# WaterLevelMonitor_v1.net
KiCad netlist of a schematic drawn in EAGLE
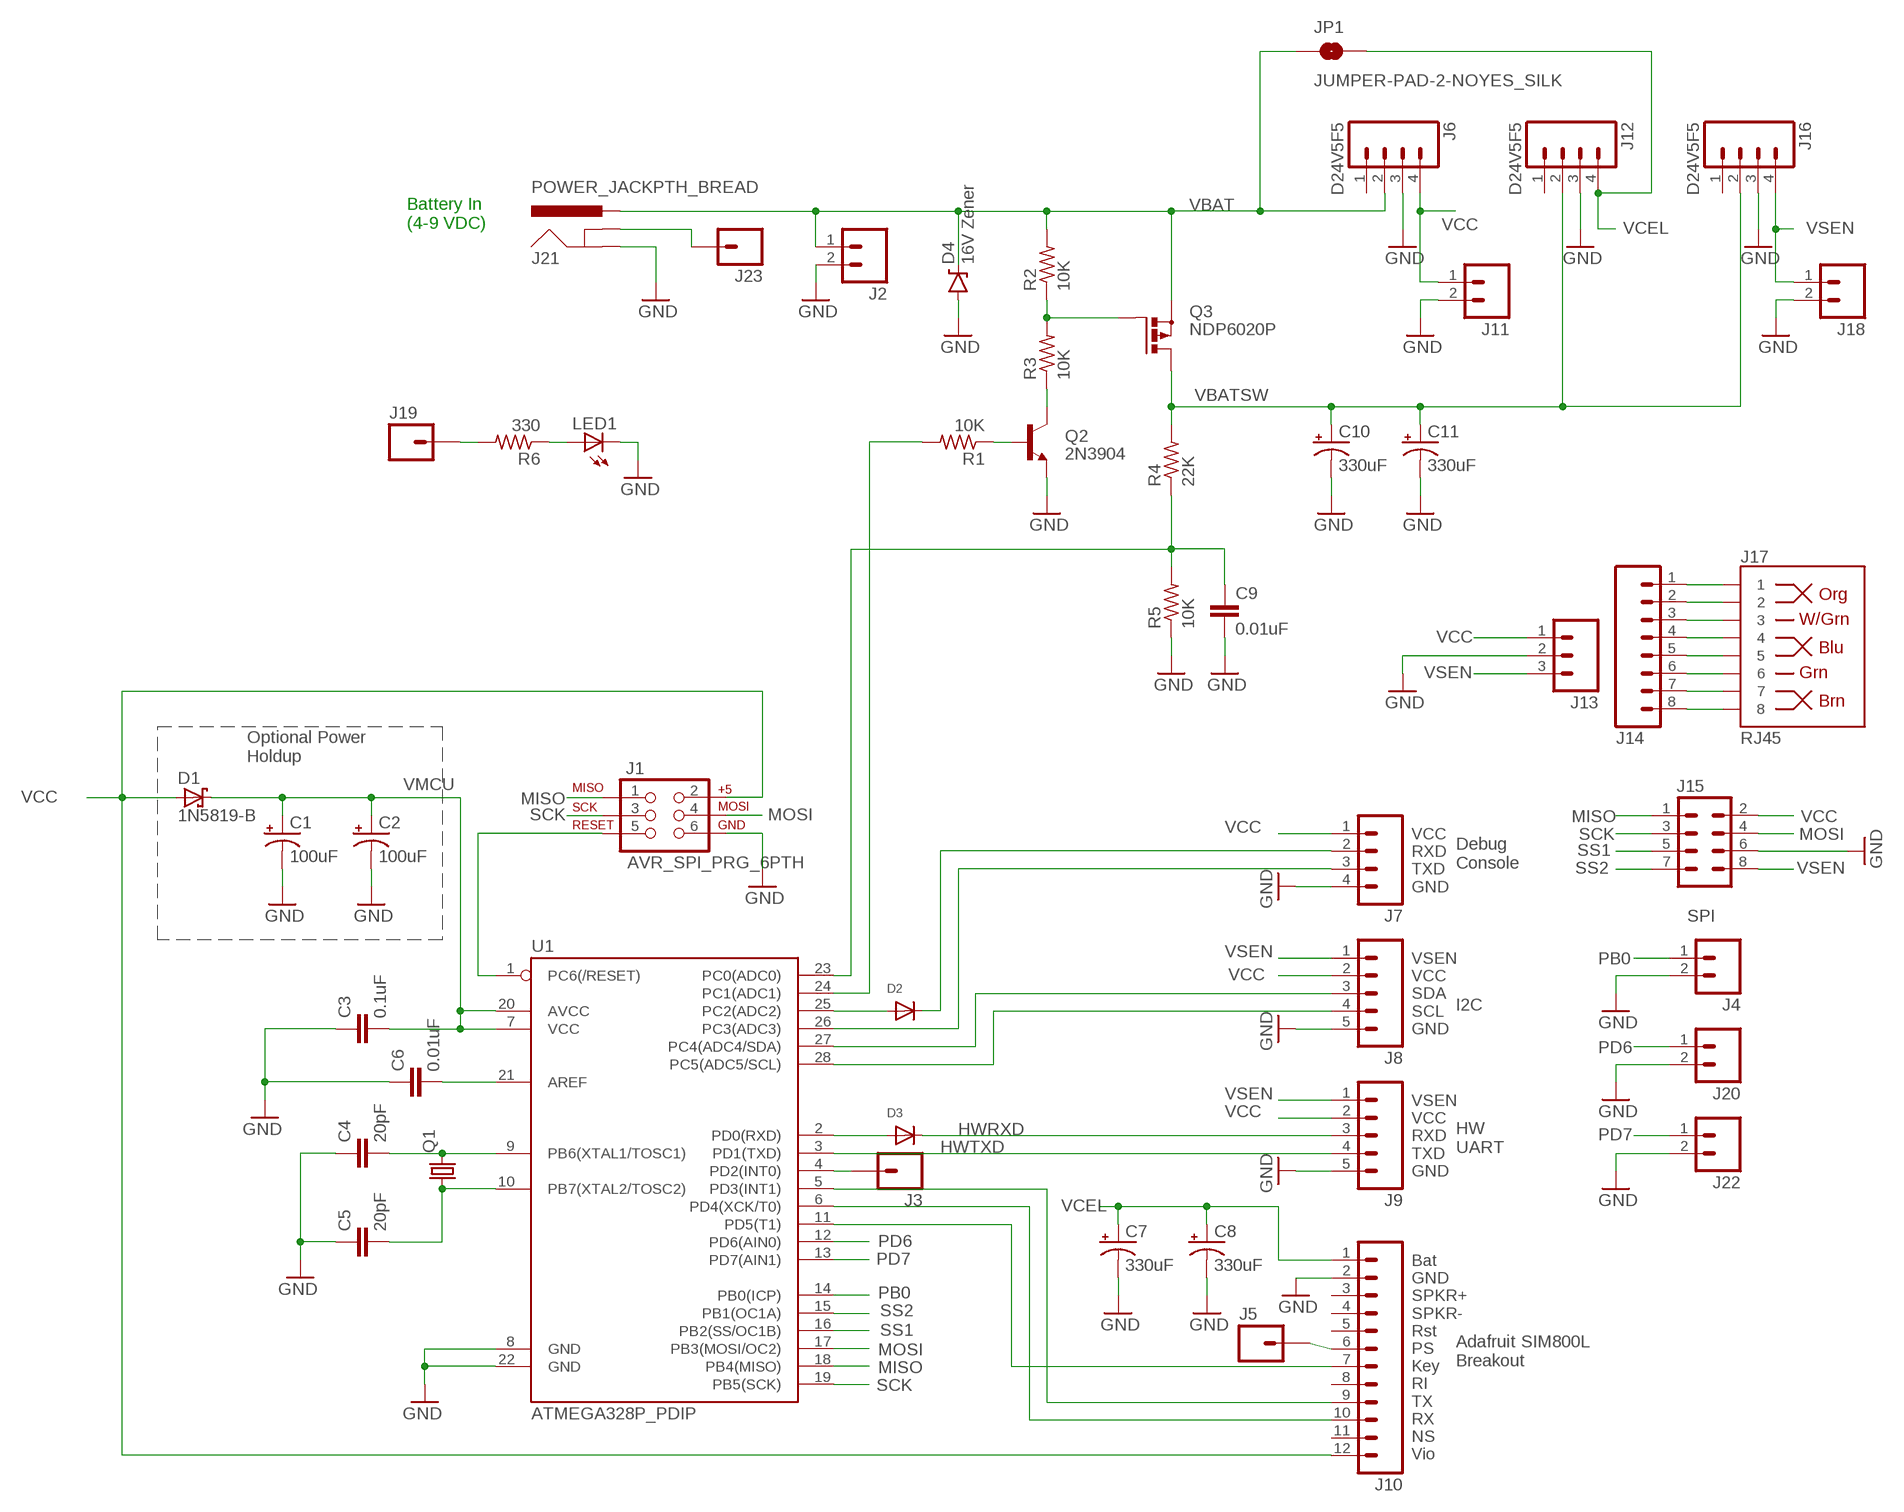
[diagram p0: schematic, sheet 1]

(export (version "E")
  (design (tool "Eeschema 10.0.6"))
  (components
    (comp (ref "C1")
      (value "100uF")
      (footprint "eagle-import:CPOL-RADIAL-100UF-25V")
      (libsource (lib "eagle-import") (part "CAP_POLPTH1"))
    )
    (comp (ref "C2")
      (value "100uF")
      (footprint "eagle-import:CPOL-RADIAL-100UF-25V")
      (libsource (lib "eagle-import") (part "CAP_POLPTH1"))
    )
    (comp (ref "C3")
      (value "0.1uF")
      (footprint "eagle-import:CAP-PTH-SMALL")
      (libsource (lib "eagle-import") (part "CAPPTH"))
    )
    (comp (ref "C4")
      (value "20pF")
      (footprint "eagle-import:CAP-PTH-SMALL")
      (libsource (lib "eagle-import") (part "CAPPTH"))
    )
    (comp (ref "C5")
      (value "20pF")
      (footprint "eagle-import:CAP-PTH-SMALL")
      (libsource (lib "eagle-import") (part "CAPPTH"))
    )
    (comp (ref "C6")
      (value "0.01uF")
      (footprint "eagle-import:CAP-PTH-5MM")
      (libsource (lib "eagle-import") (part "SparkFun-Passives_CAPPTH1"))
    )
    (comp (ref "C7")
      (value "330uF")
      (footprint "eagle-import:CPOL-RADIAL-100UF-25V")
      (libsource (lib "eagle-import") (part "CAP_POLPTH1"))
    )
    (comp (ref "C8")
      (value "330uF")
      (footprint "eagle-import:CPOL-RADIAL-100UF-25V")
      (libsource (lib "eagle-import") (part "CAP_POLPTH1"))
    )
    (comp (ref "C9")
      (value "0.01uF")
      (footprint "eagle-import:CAP-PTH-5MM")
      (libsource (lib "eagle-import") (part "SparkFun-Passives_CAPPTH1"))
    )
    (comp (ref "C10")
      (value "330uF")
      (footprint "eagle-import:CPOL-RADIAL-100UF-25V")
      (libsource (lib "eagle-import") (part "CAP_POLPTH1"))
    )
    (comp (ref "C11")
      (value "330uF")
      (footprint "eagle-import:CPOL-RADIAL-100UF-25V")
      (libsource (lib "eagle-import") (part "CAP_POLPTH1"))
    )
    (comp (ref "D1")
      (value "1N5819-B")
      (footprint "eagle-import:DO41-7.6")
      (libsource (lib "eagle-import") (part "1N5819-B"))
    )
    (comp (ref "D2")
      (value "DIODEDO-1N4148")
      (footprint "eagle-import:DO-1N4148")
      (libsource (lib "eagle-import") (part "DIODEDO-1N4148"))
    )
    (comp (ref "D3")
      (value "DIODEDO-1N4148")
      (footprint "eagle-import:DO-1N4148")
      (libsource (lib "eagle-import") (part "DIODEDO-1N4148"))
    )
    (comp (ref "D4")
      (value "16V Zener")
      (footprint "eagle-import:DIODE-ZENER")
      (libsource (lib "eagle-import") (part "DIODE-ZENERPTH"))
    )
    (comp (ref "J1")
      (value "AVR_SPI_PRG_6PTH")
      (footprint "eagle-import:2X3")
      (libsource (lib "eagle-import") (part "AVR_SPI_PRG_6PTH"))
    )
    (comp (ref "J2")
      (value "M02PTH")
      (footprint "eagle-import:1X02")
      (libsource (lib "eagle-import") (part "M02PTH"))
    )
    (comp (ref "J3")
      (value "M01PTH_NO_SILK_YES_STOP")
      (footprint "eagle-import:1X01_NO_SILK")
      (libsource (lib "eagle-import") (part "M01PTH_NO_SILK_YES_STOP"))
    )
    (comp (ref "J4")
      (value "M021X02_NO_SILK")
      (footprint "eagle-import:1X02_NO_SILK")
      (libsource (lib "eagle-import") (part "M021X02_NO_SILK"))
    )
    (comp (ref "J5")
      (value "M01PTH_NO_SILK_YES_STOP")
      (footprint "eagle-import:1X01_NO_SILK")
      (libsource (lib "eagle-import") (part "M01PTH_NO_SILK_YES_STOP"))
    )
    (comp (ref "J6")
      (value "D24V5F5")
      (footprint "eagle-import:1X04")
      (libsource (lib "eagle-import") (part "M04PTH"))
    )
    (comp (ref "J7")
      (value "M04PTH")
      (footprint "eagle-import:1X04")
      (libsource (lib "eagle-import") (part "M04PTH"))
    )
    (comp (ref "J8")
      (value "M05PTH")
      (footprint "eagle-import:1X05")
      (libsource (lib "eagle-import") (part "M05PTH"))
    )
    (comp (ref "J9")
      (value "M05PTH")
      (footprint "eagle-import:1X05")
      (libsource (lib "eagle-import") (part "M05PTH"))
    )
    (comp (ref "J10")
      (value "M12PTH")
      (footprint "eagle-import:1X12")
      (libsource (lib "eagle-import") (part "M12PTH"))
    )
    (comp (ref "J11")
      (value "M02PTH")
      (footprint "eagle-import:1X02")
      (libsource (lib "eagle-import") (part "M02PTH"))
    )
    (comp (ref "J12")
      (value "D24V5F5")
      (footprint "eagle-import:1X04")
      (libsource (lib "eagle-import") (part "M04PTH"))
    )
    (comp (ref "J13")
      (value "M03PTH")
      (footprint "eagle-import:1X03")
      (libsource (lib "eagle-import") (part "M03PTH"))
    )
    (comp (ref "J14")
      (value "M08SILK_FEMALE_PTH")
      (footprint "eagle-import:1X08")
      (libsource (lib "eagle-import") (part "M08SILK_FEMALE_PTH"))
    )
    (comp (ref "J15")
      (value "M04X2")
      (footprint "eagle-import:2X4")
      (libsource (lib "eagle-import") (part "M04X2"))
    )
    (comp (ref "J16")
      (value "D24V5F5")
      (footprint "eagle-import:1X04")
      (libsource (lib "eagle-import") (part "M04PTH"))
    )
    (comp (ref "J17")
      (value "RJ45")
      (footprint "eagle-import:RJ45-8")
      (libsource (lib "eagle-import") (part "RJ45-8PTH"))
    )
    (comp (ref "J18")
      (value "M02PTH")
      (footprint "eagle-import:1X02")
      (libsource (lib "eagle-import") (part "M02PTH"))
    )
    (comp (ref "J19")
      (value "M01PTH_NO_SILK_YES_STOP")
      (footprint "eagle-import:1X01_NO_SILK")
      (libsource (lib "eagle-import") (part "M01PTH_NO_SILK_YES_STOP"))
    )
    (comp (ref "J20")
      (value "M021X02_NO_SILK")
      (footprint "eagle-import:1X02_NO_SILK")
      (libsource (lib "eagle-import") (part "M021X02_NO_SILK"))
    )
    (comp (ref "J21")
      (value "POWER_JACKPTH_BREAD")
      (footprint "eagle-import:POWER_JACK_PTH_BREAD")
      (libsource (lib "eagle-import") (part "POWER_JACKPTH_BREAD"))
    )
    (comp (ref "J22")
      (value "M021X02_NO_SILK")
      (footprint "eagle-import:1X02_NO_SILK")
      (libsource (lib "eagle-import") (part "M021X02_NO_SILK"))
    )
    (comp (ref "J23")
      (value "M01PTH_NO_SILK_YES_STOP")
      (footprint "eagle-import:1X01_NO_SILK")
      (libsource (lib "eagle-import") (part "M01PTH_NO_SILK_YES_STOP"))
    )
    (comp (ref "JP1")
      (value "JUMPER-PAD-2-NOYES_SILK")
      (footprint "eagle-import:PAD-JUMPER-2-NO_YES_SILK")
      (libsource (lib "eagle-import") (part "JUMPER-PAD-2-NOYES_SILK"))
    )
    (comp (ref "LED1")
      (value "LED5MM")
      (footprint "eagle-import:LED5MM")
      (libsource (lib "eagle-import") (part "LED5MM"))
    )
    (comp (ref "Q1")
      (value "CRYSTALHC49U-V")
      (footprint "eagle-import:HC49U-V")
      (libsource (lib "eagle-import") (part "CRYSTALHC49U-V"))
    )
    (comp (ref "Q2")
      (value "2N3904")
      (footprint "eagle-import:TO-92-AMMO")
      (libsource (lib "eagle-import") (part "TRANSISTOR_NPNTO-92-AMMO"))
    )
    (comp (ref "Q3")
      (value "NDP6020P")
      (footprint "eagle-import:TO220BV")
      (libsource (lib "eagle-import") (part "PMOSFET_PTO220BV"))
    )
    (comp (ref "R1")
      (value "10K")
      (footprint "eagle-import:0204_5")
      (libsource (lib "eagle-import") (part "R-US_0204/5"))
    )
    (comp (ref "R2")
      (value "10K")
      (footprint "eagle-import:0204_5")
      (libsource (lib "eagle-import") (part "R-US_0204/5"))
    )
    (comp (ref "R3")
      (value "10K")
      (footprint "eagle-import:0204_5")
      (libsource (lib "eagle-import") (part "R-US_0204/5"))
    )
    (comp (ref "R4")
      (value "22K")
      (footprint "eagle-import:0204_5")
      (libsource (lib "eagle-import") (part "R-US_0204/5"))
    )
    (comp (ref "R5")
      (value "10K")
      (footprint "eagle-import:0204_5")
      (libsource (lib "eagle-import") (part "R-US_0204/5"))
    )
    (comp (ref "R6")
      (value "330")
      (footprint "eagle-import:0204_5")
      (libsource (lib "eagle-import") (part "R-US_0204/5"))
    )
    (comp (ref "U1")
      (value "ATMEGA328P_PDIP")
      (footprint "eagle-import:DIL28-3")
      (libsource (lib "eagle-import") (part "ATMEGA328P_PDIP"))
    )
  )
  (nets
    (net (code "1") (name "/HWRXD") (class "Default")
      (node (ref "D3") (pin "C") (pinfunction "C_C") (pintype "passive"))
      (node (ref "J9") (pin "3") (pinfunction "3_3") (pintype "passive"))
    )
    (net (code "2") (name "/HWTXD") (class "Default")
      (node (ref "J9") (pin "4") (pinfunction "4_4") (pintype "passive"))
      (node (ref "U1") (pin "3") (pinfunction "PD1(TXD)_3") (pintype "bidirectional"))
    )
    (net (code "3") (name "/MISO") (class "Default")
      (node (ref "J1") (pin "1") (pinfunction "1_1") (pintype "passive"))
      (node (ref "J15") (pin "1") (pinfunction "1_1") (pintype "passive"))
      (node (ref "U1") (pin "18") (pinfunction "PB4(MISO)_18") (pintype "bidirectional"))
    )
    (net (code "4") (name "/MOSI") (class "Default")
      (node (ref "J1") (pin "4") (pinfunction "4_4") (pintype "passive"))
      (node (ref "J15") (pin "4") (pinfunction "4_4") (pintype "passive"))
      (node (ref "U1") (pin "17") (pinfunction "PB3(MOSI/OC2)_17") (pintype "bidirectional"))
    )
    (net (code "5") (name "/PB0") (class "Default")
      (node (ref "J4") (pin "1") (pinfunction "1_1") (pintype "passive"))
      (node (ref "U1") (pin "14") (pinfunction "PB0(ICP)_14") (pintype "bidirectional"))
    )
    (net (code "6") (name "/PD6") (class "Default")
      (node (ref "J20") (pin "1") (pinfunction "1_1") (pintype "passive"))
      (node (ref "U1") (pin "12") (pinfunction "PD6(AIN0)_12") (pintype "bidirectional"))
    )
    (net (code "7") (name "/PD7") (class "Default")
      (node (ref "J22") (pin "1") (pinfunction "1_1") (pintype "passive"))
      (node (ref "U1") (pin "13") (pinfunction "PD7(AIN1)_13") (pintype "bidirectional"))
    )
    (net (code "8") (name "/SCK") (class "Default")
      (node (ref "J1") (pin "3") (pinfunction "3_3") (pintype "passive"))
      (node (ref "J15") (pin "3") (pinfunction "3_3") (pintype "passive"))
      (node (ref "U1") (pin "19") (pinfunction "PB5(SCK)_19") (pintype "bidirectional"))
    )
    (net (code "9") (name "/SS1") (class "Default")
      (node (ref "J15") (pin "5") (pinfunction "5_5") (pintype "passive"))
      (node (ref "U1") (pin "16") (pinfunction "PB2(SS/OC1B)_16") (pintype "bidirectional"))
    )
    (net (code "10") (name "/SS2") (class "Default")
      (node (ref "J15") (pin "7") (pinfunction "7_7") (pintype "passive"))
      (node (ref "U1") (pin "15") (pinfunction "PB1(OC1A)_15") (pintype "bidirectional"))
    )
    (net (code "11") (name "/VBAT") (class "Default")
      (node (ref "D4") (pin "P$1") (pinfunction "C_P$1") (pintype "passive"))
      (node (ref "J2") (pin "1") (pinfunction "1_1") (pintype "passive"))
      (node (ref "J21") (pin "PWR") (pinfunction "PWR_PWR") (pintype "bidirectional"))
      (node (ref "J6") (pin "2") (pinfunction "2_2") (pintype "passive"))
      (node (ref "JP1") (pin "1") (pinfunction "1_1") (pintype "passive"))
      (node (ref "Q3") (pin "S") (pinfunction "S_S") (pintype "passive"))
      (node (ref "R2") (pin "2") (pinfunction "2_2") (pintype "passive"))
    )
    (net (code "12") (name "/VBATSW") (class "Default")
      (node (ref "C10") (pin "1") (pinfunction "+_1") (pintype "passive"))
      (node (ref "C11") (pin "1") (pinfunction "+_1") (pintype "passive"))
      (node (ref "J12") (pin "2") (pinfunction "2_2") (pintype "passive"))
      (node (ref "J16") (pin "2") (pinfunction "2_2") (pintype "passive"))
      (node (ref "Q3") (pin "D") (pinfunction "D_D") (pintype "passive"))
      (node (ref "R4") (pin "2") (pinfunction "2_2") (pintype "passive"))
    )
    (net (code "13") (name "/VCC") (class "Default")
      (node (ref "D1") (pin "A") (pinfunction "A_A") (pintype "passive"))
      (node (ref "J1") (pin "2") (pinfunction "2_2") (pintype "passive"))
      (node (ref "J10") (pin "12") (pinfunction "12_12") (pintype "passive"))
      (node (ref "J11") (pin "1") (pinfunction "1_1") (pintype "passive"))
      (node (ref "J13") (pin "1") (pinfunction "1_1") (pintype "passive"))
      (node (ref "J15") (pin "2") (pinfunction "2_2") (pintype "passive"))
      (node (ref "J6") (pin "4") (pinfunction "4_4") (pintype "passive"))
      (node (ref "J7") (pin "1") (pinfunction "1_1") (pintype "passive"))
      (node (ref "J8") (pin "2") (pinfunction "2_2") (pintype "passive"))
      (node (ref "J9") (pin "2") (pinfunction "2_2") (pintype "passive"))
    )
    (net (code "14") (name "/VCEL") (class "Default")
      (node (ref "C7") (pin "1") (pinfunction "+_1") (pintype "passive"))
      (node (ref "C8") (pin "1") (pinfunction "+_1") (pintype "passive"))
      (node (ref "J10") (pin "1") (pinfunction "1_1") (pintype "passive"))
      (node (ref "J12") (pin "4") (pinfunction "4_4") (pintype "passive"))
      (node (ref "JP1") (pin "2") (pinfunction "2_2") (pintype "passive"))
    )
    (net (code "15") (name "/VMCU") (class "Default")
      (node (ref "C1") (pin "1") (pinfunction "+_1") (pintype "passive"))
      (node (ref "C2") (pin "1") (pinfunction "+_1") (pintype "passive"))
      (node (ref "C3") (pin "2") (pinfunction "2_2") (pintype "passive"))
      (node (ref "D1") (pin "C") (pinfunction "C_C") (pintype "passive"))
      (node (ref "U1") (pin "20") (pinfunction "AVCC_20") (pintype "bidirectional"))
      (node (ref "U1") (pin "7") (pinfunction "VCC_7") (pintype "bidirectional"))
    )
    (net (code "16") (name "/VSEN") (class "Default")
      (node (ref "J13") (pin "3") (pinfunction "3_3") (pintype "passive"))
      (node (ref "J15") (pin "8") (pinfunction "8_8") (pintype "passive"))
      (node (ref "J16") (pin "4") (pinfunction "4_4") (pintype "passive"))
      (node (ref "J18") (pin "1") (pinfunction "1_1") (pintype "passive"))
      (node (ref "J8") (pin "1") (pinfunction "1_1") (pintype "passive"))
      (node (ref "J9") (pin "1") (pinfunction "1_1") (pintype "passive"))
    )
    (net (code "17") (name "GND") (class "Default")
      (node (ref "C1") (pin "2") (pinfunction "-_2") (pintype "passive"))
      (node (ref "C10") (pin "2") (pinfunction "-_2") (pintype "passive"))
      (node (ref "C11") (pin "2") (pinfunction "-_2") (pintype "passive"))
      (node (ref "C2") (pin "2") (pinfunction "-_2") (pintype "passive"))
      (node (ref "C3") (pin "1") (pinfunction "1_1") (pintype "passive"))
      (node (ref "C4") (pin "1") (pinfunction "1_1") (pintype "passive"))
      (node (ref "C5") (pin "1") (pinfunction "1_1") (pintype "passive"))
      (node (ref "C6") (pin "1") (pinfunction "1_1") (pintype "passive"))
      (node (ref "C7") (pin "2") (pinfunction "-_2") (pintype "passive"))
      (node (ref "C8") (pin "2") (pinfunction "-_2") (pintype "passive"))
      (node (ref "C9") (pin "2") (pinfunction "2_2") (pintype "passive"))
      (node (ref "D4") (pin "P$2") (pinfunction "A_P$2") (pintype "passive"))
      (node (ref "J1") (pin "6") (pinfunction "6_6") (pintype "passive"))
      (node (ref "J10") (pin "2") (pinfunction "2_2") (pintype "passive"))
      (node (ref "J11") (pin "2") (pinfunction "2_2") (pintype "passive"))
      (node (ref "J12") (pin "3") (pinfunction "3_3") (pintype "passive"))
      (node (ref "J13") (pin "2") (pinfunction "2_2") (pintype "passive"))
      (node (ref "J15") (pin "6") (pinfunction "6_6") (pintype "passive"))
      (node (ref "J16") (pin "3") (pinfunction "3_3") (pintype "passive"))
      (node (ref "J18") (pin "2") (pinfunction "2_2") (pintype "passive"))
      (node (ref "J2") (pin "2") (pinfunction "2_2") (pintype "passive"))
      (node (ref "J20") (pin "2") (pinfunction "2_2") (pintype "passive"))
      (node (ref "J21") (pin "GND") (pinfunction "GND_GND") (pintype "bidirectional"))
      (node (ref "J22") (pin "2") (pinfunction "2_2") (pintype "passive"))
      (node (ref "J4") (pin "2") (pinfunction "2_2") (pintype "passive"))
      (node (ref "J6") (pin "3") (pinfunction "3_3") (pintype "passive"))
      (node (ref "J7") (pin "4") (pinfunction "4_4") (pintype "passive"))
      (node (ref "J8") (pin "5") (pinfunction "5_5") (pintype "passive"))
      (node (ref "J9") (pin "5") (pinfunction "5_5") (pintype "passive"))
      (node (ref "LED1") (pin "K") (pinfunction "C_K") (pintype "passive"))
      (node (ref "Q2") (pin "1") (pinfunction "E_1") (pintype "passive"))
      (node (ref "R5") (pin "1") (pinfunction "1_1") (pintype "passive"))
      (node (ref "U1") (pin "22") (pinfunction "GND_22") (pintype "bidirectional"))
      (node (ref "U1") (pin "8") (pinfunction "GND_8") (pintype "bidirectional"))
    )
    (net (code "18") (name "Net-(D2-PadC)") (class "Default")
      (node (ref "D2") (pin "C") (pinfunction "C_C") (pintype "passive"))
      (node (ref "J7") (pin "2") (pinfunction "2_2") (pintype "passive"))
    )
    (net (code "19") (name "Net-(J10-Pad6)") (class "Default")
      (node (ref "J10") (pin "6") (pinfunction "6_6") (pintype "passive"))
      (node (ref "J5") (pin "1") (pinfunction "1_1") (pintype "passive"))
    )
    (net (code "20") (name "Net-(J14-Pad1)") (class "Default")
      (node (ref "J14") (pin "1") (pinfunction "1_1") (pintype "passive"))
      (node (ref "J17") (pin "1") (pinfunction "1_1") (pintype "bidirectional"))
    )
    (net (code "21") (name "Net-(J14-Pad2)") (class "Default")
      (node (ref "J14") (pin "2") (pinfunction "2_2") (pintype "passive"))
      (node (ref "J17") (pin "2") (pinfunction "2_2") (pintype "bidirectional"))
    )
    (net (code "22") (name "Net-(J14-Pad3)") (class "Default")
      (node (ref "J14") (pin "3") (pinfunction "3_3") (pintype "passive"))
      (node (ref "J17") (pin "3") (pinfunction "3_3") (pintype "bidirectional"))
    )
    (net (code "23") (name "Net-(J14-Pad4)") (class "Default")
      (node (ref "J14") (pin "4") (pinfunction "4_4") (pintype "passive"))
      (node (ref "J17") (pin "4") (pinfunction "4_4") (pintype "bidirectional"))
    )
    (net (code "24") (name "Net-(J14-Pad5)") (class "Default")
      (node (ref "J14") (pin "5") (pinfunction "5_5") (pintype "passive"))
      (node (ref "J17") (pin "5") (pinfunction "5_5") (pintype "bidirectional"))
    )
    (net (code "25") (name "Net-(J14-Pad6)") (class "Default")
      (node (ref "J14") (pin "6") (pinfunction "6_6") (pintype "passive"))
      (node (ref "J17") (pin "6") (pinfunction "6_6") (pintype "bidirectional"))
    )
    (net (code "26") (name "Net-(J14-Pad7)") (class "Default")
      (node (ref "J14") (pin "7") (pinfunction "7_7") (pintype "passive"))
      (node (ref "J17") (pin "7") (pinfunction "7_7") (pintype "bidirectional"))
    )
    (net (code "27") (name "Net-(J14-Pad8)") (class "Default")
      (node (ref "J14") (pin "8") (pinfunction "8_8") (pintype "passive"))
      (node (ref "J17") (pin "8") (pinfunction "8_8") (pintype "bidirectional"))
    )
    (net (code "28") (name "Net-(J19-Pad1)") (class "Default")
      (node (ref "J19") (pin "1") (pinfunction "1_1") (pintype "passive"))
      (node (ref "R6") (pin "2") (pinfunction "2_2") (pintype "passive"))
    )
    (net (code "29") (name "Net-(J21-PadGNDBREAK)") (class "Default")
      (node (ref "J21") (pin "GNDBREAK") (pinfunction "GNDBREAK_GNDBREAK") (pintype "bidirectional"))
      (node (ref "J23") (pin "1") (pinfunction "1_1") (pintype "passive"))
    )
    (net (code "30") (name "Net-(LED1-PadA)") (class "Default")
      (node (ref "LED1") (pin "A") (pinfunction "A_A") (pintype "passive"))
      (node (ref "R6") (pin "1") (pinfunction "1_1") (pintype "passive"))
    )
    (net (code "31") (name "Net-(Q2-B)") (class "Default")
      (node (ref "Q2") (pin "2") (pinfunction "B_2") (pintype "passive"))
      (node (ref "R1") (pin "1") (pinfunction "1_1") (pintype "passive"))
    )
    (net (code "32") (name "Net-(Q2-C)") (class "Default")
      (node (ref "Q2") (pin "3") (pinfunction "C_3") (pintype "passive"))
      (node (ref "R3") (pin "1") (pinfunction "1_1") (pintype "passive"))
    )
    (net (code "33") (name "Net-(Q3-PadG)") (class "Default")
      (node (ref "Q3") (pin "G") (pinfunction "G_G") (pintype "passive"))
      (node (ref "R2") (pin "1") (pinfunction "1_1") (pintype "passive"))
      (node (ref "R3") (pin "2") (pinfunction "2_2") (pintype "passive"))
    )
    (net (code "34") (name "Net-(U1-AREF)") (class "Default")
      (node (ref "C6") (pin "2") (pinfunction "2_2") (pintype "passive"))
      (node (ref "U1") (pin "21") (pinfunction "AREF_21") (pintype "bidirectional"))
    )
    (net (code "35") (name "Net-(U1-PB6(XTAL1{slash}TOSC1))") (class "Default")
      (node (ref "C4") (pin "2") (pinfunction "2_2") (pintype "passive"))
      (node (ref "Q1") (pin "2") (pinfunction "2_2") (pintype "passive"))
      (node (ref "U1") (pin "9") (pinfunction "PB6(XTAL1/TOSC1)_9") (pintype "bidirectional"))
    )
    (net (code "36") (name "Net-(U1-PB7(XTAL2{slash}TOSC2))") (class "Default")
      (node (ref "C5") (pin "2") (pinfunction "2_2") (pintype "passive"))
      (node (ref "Q1") (pin "1") (pinfunction "1_1") (pintype "passive"))
      (node (ref "U1") (pin "10") (pinfunction "PB7(XTAL2/TOSC2)_10") (pintype "bidirectional"))
    )
    (net (code "37") (name "Net-(U1-PC0(ADC0))") (class "Default")
      (node (ref "C9") (pin "1") (pinfunction "1_1") (pintype "passive"))
      (node (ref "R4") (pin "1") (pinfunction "1_1") (pintype "passive"))
      (node (ref "R5") (pin "2") (pinfunction "2_2") (pintype "passive"))
      (node (ref "U1") (pin "23") (pinfunction "PC0(ADC0)_23") (pintype "bidirectional"))
    )
    (net (code "38") (name "Net-(U1-PC1(ADC1))") (class "Default")
      (node (ref "R1") (pin "2") (pinfunction "2_2") (pintype "passive"))
      (node (ref "U1") (pin "24") (pinfunction "PC1(ADC1)_24") (pintype "bidirectional"))
    )
    (net (code "39") (name "Net-(U1-PC2(ADC2))") (class "Default")
      (node (ref "D2") (pin "A") (pinfunction "A_A") (pintype "passive"))
      (node (ref "U1") (pin "25") (pinfunction "PC2(ADC2)_25") (pintype "bidirectional"))
    )
    (net (code "40") (name "Net-(U1-PC3(ADC3))") (class "Default")
      (node (ref "J7") (pin "3") (pinfunction "3_3") (pintype "passive"))
      (node (ref "U1") (pin "26") (pinfunction "PC3(ADC3)_26") (pintype "bidirectional"))
    )
    (net (code "41") (name "Net-(U1-PC4(ADC4{slash}SDA))") (class "Default")
      (node (ref "J8") (pin "3") (pinfunction "3_3") (pintype "passive"))
      (node (ref "U1") (pin "27") (pinfunction "PC4(ADC4/SDA)_27") (pintype "bidirectional"))
    )
    (net (code "42") (name "Net-(U1-PC5(ADC5{slash}SCL))") (class "Default")
      (node (ref "J8") (pin "4") (pinfunction "4_4") (pintype "passive"))
      (node (ref "U1") (pin "28") (pinfunction "PC5(ADC5/SCL)_28") (pintype "bidirectional"))
    )
    (net (code "43") (name "Net-(U1-PC6({slash}RESET))") (class "Default")
      (node (ref "J1") (pin "5") (pinfunction "5_5") (pintype "passive"))
      (node (ref "U1") (pin "1") (pinfunction "PC6(/RESET)_1") (pintype "bidirectional"))
    )
    (net (code "44") (name "Net-(U1-PD0(RXD))") (class "Default")
      (node (ref "D3") (pin "A") (pinfunction "A_A") (pintype "passive"))
      (node (ref "U1") (pin "2") (pinfunction "PD0(RXD)_2") (pintype "bidirectional"))
    )
    (net (code "45") (name "Net-(U1-PD2(INT0))") (class "Default")
      (node (ref "J3") (pin "1") (pinfunction "1_1") (pintype "passive"))
      (node (ref "U1") (pin "4") (pinfunction "PD2(INT0)_4") (pintype "bidirectional"))
    )
    (net (code "46") (name "Net-(U1-PD3(INT1))") (class "Default")
      (node (ref "J10") (pin "9") (pinfunction "9_9") (pintype "passive"))
      (node (ref "U1") (pin "5") (pinfunction "PD3(INT1)_5") (pintype "bidirectional"))
    )
    (net (code "47") (name "Net-(U1-PD4(XCK{slash}T0))") (class "Default")
      (node (ref "J10") (pin "10") (pinfunction "10_10") (pintype "passive"))
      (node (ref "U1") (pin "6") (pinfunction "PD4(XCK/T0)_6") (pintype "bidirectional"))
    )
    (net (code "48") (name "Net-(U1-PD5(T1))") (class "Default")
      (node (ref "J10") (pin "7") (pinfunction "7_7") (pintype "passive"))
      (node (ref "U1") (pin "11") (pinfunction "PD5(T1)_11") (pintype "bidirectional"))
    )
    (net (code "49") (name "unconnected-(J6-Pad1)") (class "Default")
      (node (ref "J6") (pin "1") (pinfunction "1_1") (pintype "passive"))
    )
    (net (code "50") (name "unconnected-(J10-Pad3)") (class "Default")
      (node (ref "J10") (pin "3") (pinfunction "3_3") (pintype "passive"))
    )
    (net (code "51") (name "unconnected-(J10-Pad4)") (class "Default")
      (node (ref "J10") (pin "4") (pinfunction "4_4") (pintype "passive"))
    )
    (net (code "52") (name "unconnected-(J10-Pad5)") (class "Default")
      (node (ref "J10") (pin "5") (pinfunction "5_5") (pintype "passive"))
    )
    (net (code "53") (name "unconnected-(J10-Pad8)") (class "Default")
      (node (ref "J10") (pin "8") (pinfunction "8_8") (pintype "passive"))
    )
    (net (code "54") (name "unconnected-(J10-Pad11)") (class "Default")
      (node (ref "J10") (pin "11") (pinfunction "11_11") (pintype "passive"))
    )
    (net (code "55") (name "unconnected-(J12-Pad1)") (class "Default")
      (node (ref "J12") (pin "1") (pinfunction "1_1") (pintype "passive"))
    )
    (net (code "56") (name "unconnected-(J16-Pad1)") (class "Default")
      (node (ref "J16") (pin "1") (pinfunction "1_1") (pintype "passive"))
    )
  )
)
